# Batt_Meas.net
KiCad netlist of a schematic drawn in Altium Designer
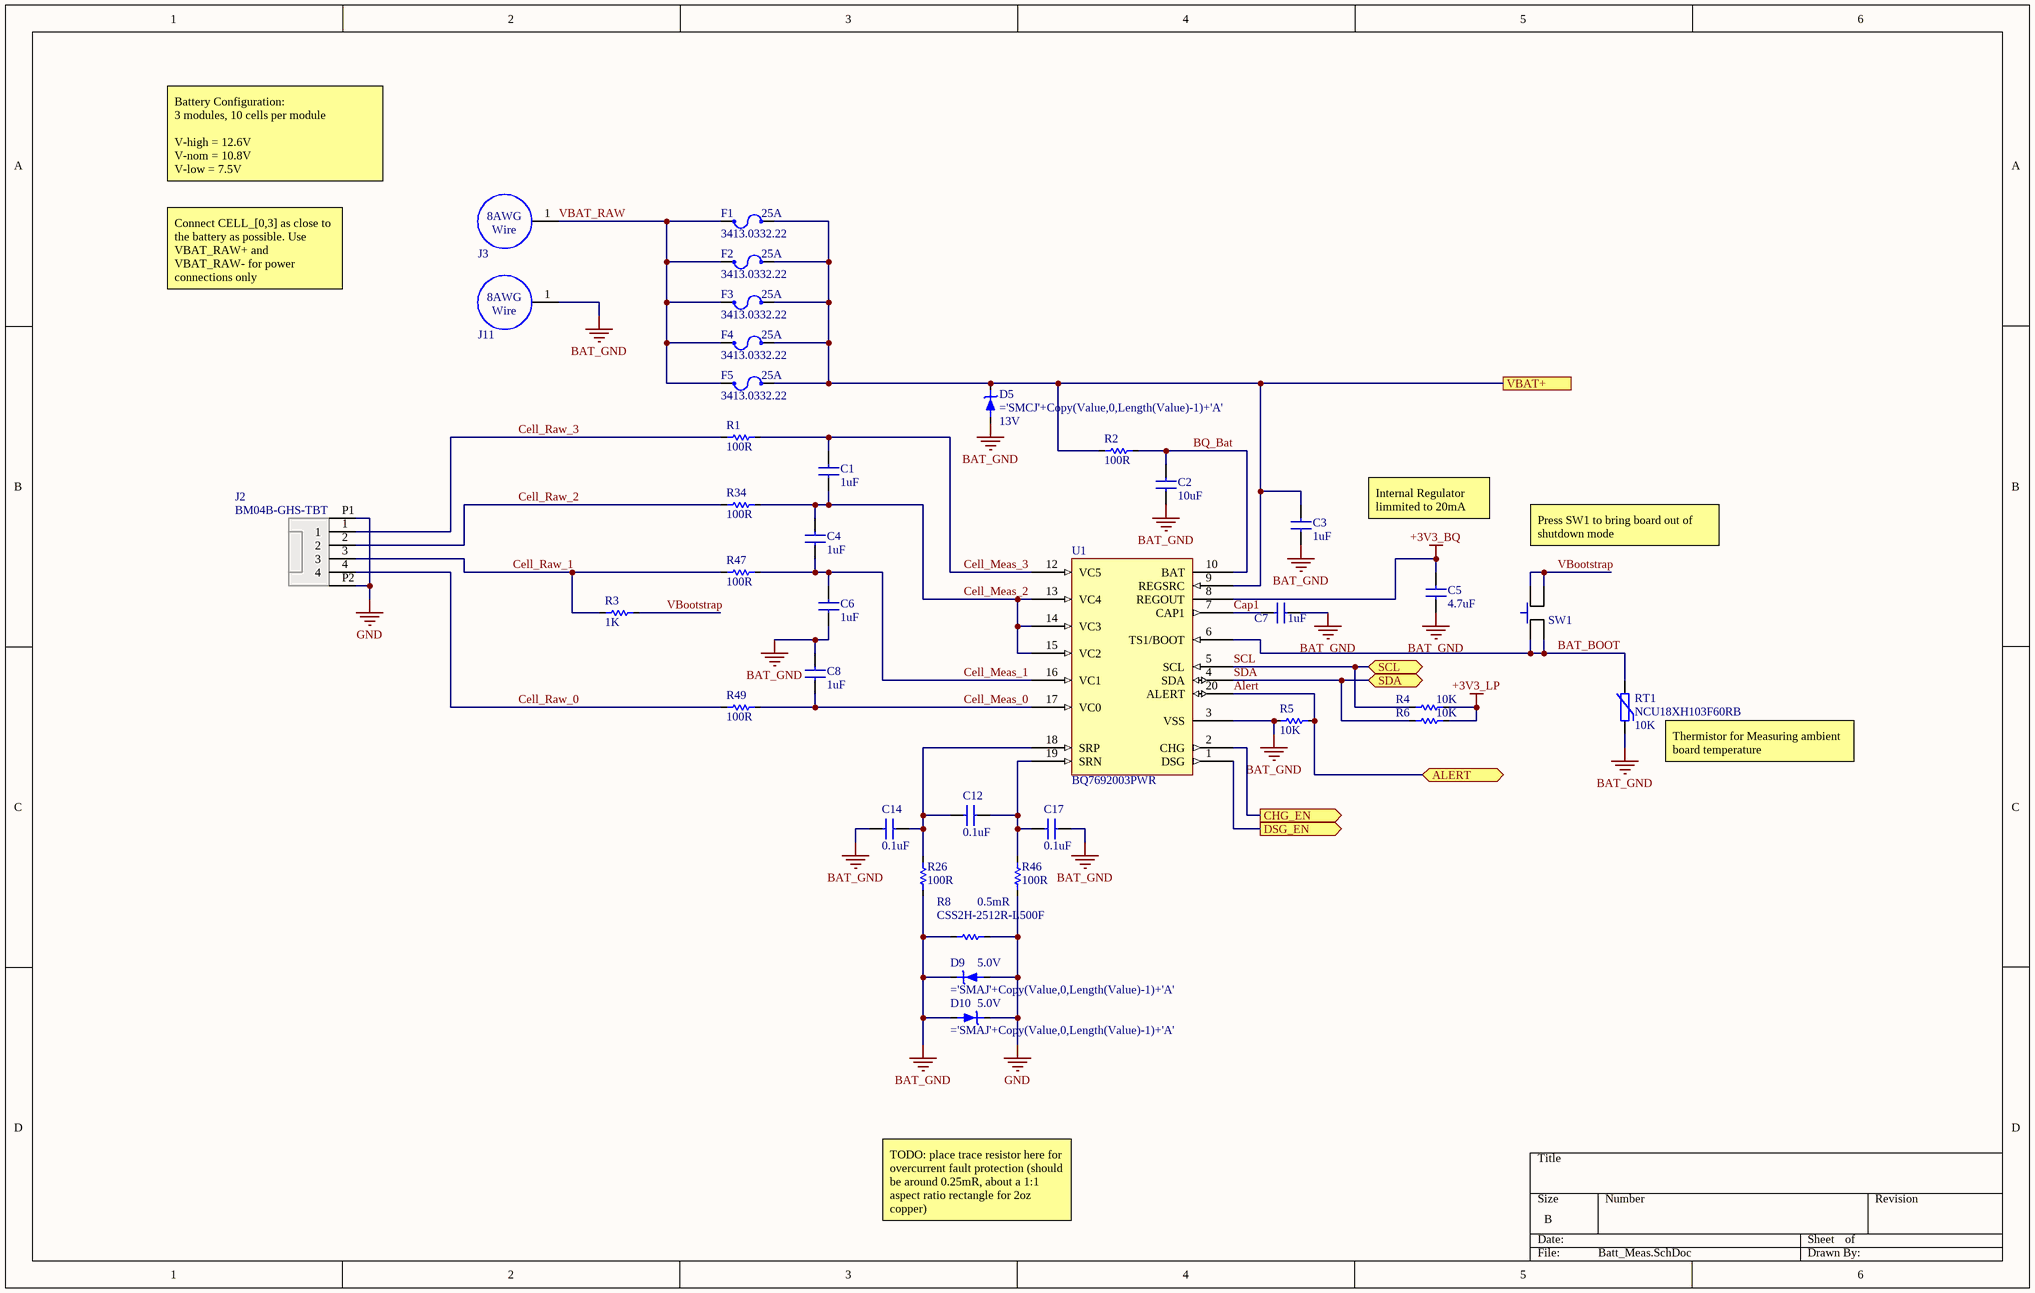
[diagram p0: Batt_Meas.SchDoc]

(export (version "E")
  (design (tool "Eeschema 10.0.6"))
  (components
    (comp (ref "C1")
      (value "1uF")
      (footprint "0603_CAPACITOR")
      (description "CAP CERM 1uF 10% 16V 0603")
      (fields
        (field (name "VOLTAGE") "16V")
        (field (name "Comment") "CAP 1uF 16V X7R")
        (field (name "SVP CREATOR") "Spencer Berglund")
      )
      (libsource (lib "capacitor") (part "C_0603_1uF_16V_10%"))
    )
    (comp (ref "C2")
      (value "10uF")
      (footprint "1206_CAPACITOR")
      (description "CAP CERM 10uF 20% 50V 1206")
      (fields
        (field (name "VOLTAGE") "50V")
        (field (name "Comment") "CAP 10uF 50V X5R")
        (field (name "SVP CREATOR") "Spencer Berglund")
      )
      (libsource (lib "capacitor") (part "C_1206_10uF_50V_20%"))
    )
    (comp (ref "C3")
      (value "1uF")
      (footprint "0603_CAPACITOR")
      (description "CAP CERM 1uF 10% 16V 0603")
      (fields
        (field (name "VOLTAGE") "16V")
        (field (name "Comment") "CAP 1uF 16V X7R")
        (field (name "SVP CREATOR") "Spencer Berglund")
      )
      (libsource (lib "capacitor") (part "C_0603_1uF_16V_10%"))
    )
    (comp (ref "C4")
      (value "1uF")
      (footprint "0603_CAPACITOR")
      (description "CAP CERM 1uF 10% 16V 0603")
      (fields
        (field (name "VOLTAGE") "16V")
        (field (name "Comment") "CAP 1uF 16V X7R")
        (field (name "SVP CREATOR") "Spencer Berglund")
      )
      (libsource (lib "capacitor") (part "C_0603_1uF_16V_10%"))
    )
    (comp (ref "C5")
      (value "4.7uF")
      (footprint "0603_Capacitor")
      (description "CAP CER 4.7UF 6.3V X5R 0603")
      (fields (field (name "VOLTAGE") "6.3V") (field (name "Comment") "CAP 4.7uF 6.3V X5R"))
      (libsource (lib "capacitor") (part "C_0603_4.7uF_6.3V_10%"))
    )
    (comp (ref "C6")
      (value "1uF")
      (footprint "0603_CAPACITOR")
      (description "CAP CERM 1uF 10% 16V 0603")
      (fields
        (field (name "VOLTAGE") "16V")
        (field (name "Comment") "CAP 1uF 16V X7R")
        (field (name "SVP CREATOR") "Spencer Berglund")
      )
      (libsource (lib "capacitor") (part "C_0603_1uF_16V_10%"))
    )
    (comp (ref "C7")
      (value "1uF")
      (footprint "0805_Capacitor")
      (description "CAP CERM 1uF 10% 16V 0805")
      (fields
        (field (name "VOLTAGE") "16V")
        (field (name "Comment") "CAP 1uF 16V X7R")
        (field (name "SVP CREATOR") "Spencer Berglund")
      )
      (libsource (lib "capacitor") (part "C_0805_1uF_16V_10%"))
    )
    (comp (ref "C8")
      (value "1uF")
      (footprint "0603_CAPACITOR")
      (description "CAP CERM 1uF 10% 16V 0603")
      (fields
        (field (name "VOLTAGE") "16V")
        (field (name "Comment") "CAP 1uF 16V X7R")
        (field (name "SVP CREATOR") "Spencer Berglund")
      )
      (libsource (lib "capacitor") (part "C_0603_1uF_16V_10%"))
    )
    (comp (ref "C12")
      (value "0.1uF")
      (footprint "0402_CAPACITOR")
      (description "CAP CERM 0.1uF 10% 16V 0402")
      (fields (field (name "VOLTAGE") "16V") (field (name "Comment") "CAP 0.1uF 16V X7R"))
      (libsource (lib "capacitor") (part "C_0402_0.1uF_16V_10%"))
    )
    (comp (ref "C14")
      (value "0.1uF")
      (footprint "0402_CAPACITOR")
      (description "CAP CERM 0.1uF 10% 16V 0402")
      (fields (field (name "VOLTAGE") "16V") (field (name "Comment") "CAP 0.1uF 16V X7R"))
      (libsource (lib "capacitor") (part "C_0402_0.1uF_16V_10%"))
    )
    (comp (ref "C17")
      (value "0.1uF")
      (footprint "0402_CAPACITOR")
      (description "CAP CERM 0.1uF 10% 16V 0402")
      (fields (field (name "VOLTAGE") "16V") (field (name "Comment") "CAP 0.1uF 16V X7R"))
      (libsource (lib "capacitor") (part "C_0402_0.1uF_16V_10%"))
    )
    (comp (ref "D5")
      (value "13V")
      (footprint "SMC")
      (description "SMC Unidirectional TVS Diode")
      (fields
        (field (name "MANUFACTURER") "Vishay")
        (field (name "MANUFACTURER PN") "SMCJA")
        (field (name "Comment") "TVS Diode")
      )
      (libsource (lib "diode") (part "D_TVS_SMCJ_Uni_generic"))
    )
    (comp (ref "D9")
      (value "5.0V")
      (footprint "SMA")
      (description "SMA Unidirectional TVS Diode")
      (fields
        (field (name "MANUFACTURER") "Vishay")
        (field (name "MANUFACTURER PN") "SMAJA")
        (field (name "Comment") "TVS Diode")
      )
      (libsource (lib "diode") (part "D_TVS_SMAJ_Uni_generic"))
    )
    (comp (ref "D10")
      (value "5.0V")
      (footprint "SMA")
      (description "SMA Unidirectional TVS Diode")
      (fields
        (field (name "MANUFACTURER") "Vishay")
        (field (name "MANUFACTURER PN") "SMAJA")
        (field (name "Comment") "TVS Diode")
      )
      (libsource (lib "diode") (part "D_TVS_SMAJ_Uni_generic"))
    )
    (comp (ref "F1")
      (value "3413.0332.22")
      (footprint "1206_Fuse")
      (description "FUSE BOARD MOUNT 25A 32VAC 63VDC")
      (fields (field (name "ALTIUM_VALUE") "25A"))
      (libsource (lib "fuse") (part "F_3413.0332.22"))
    )
    (comp (ref "F2")
      (value "3413.0332.22")
      (footprint "1206_Fuse")
      (description "FUSE BOARD MOUNT 25A 32VAC 63VDC")
      (fields (field (name "ALTIUM_VALUE") "25A"))
      (libsource (lib "fuse") (part "F_3413.0332.22"))
    )
    (comp (ref "F3")
      (value "3413.0332.22")
      (footprint "1206_Fuse")
      (description "FUSE BOARD MOUNT 25A 32VAC 63VDC")
      (fields (field (name "ALTIUM_VALUE") "25A"))
      (libsource (lib "fuse") (part "F_3413.0332.22"))
    )
    (comp (ref "F4")
      (value "3413.0332.22")
      (footprint "1206_Fuse")
      (description "FUSE BOARD MOUNT 25A 32VAC 63VDC")
      (fields (field (name "ALTIUM_VALUE") "25A"))
      (libsource (lib "fuse") (part "F_3413.0332.22"))
    )
    (comp (ref "F5")
      (value "3413.0332.22")
      (footprint "1206_Fuse")
      (description "FUSE BOARD MOUNT 25A 32VAC 63VDC")
      (fields (field (name "ALTIUM_VALUE") "25A"))
      (libsource (lib "fuse") (part "F_3413.0332.22"))
    )
    (comp (ref "J2")
      (value "BM04B-GHS-TBT")
      (footprint "J_BM04B-GHS-TBT")
      (description "Connector Header Surface Mount 4 position 0.049\" (1.25mm)")
      (fields
        (field (name "MANUFACTURER") "JST")
        (field (name "MANUFACTURER PART NUMBER") "BM04B-GHS-TBT(LF)(SN)")
      )
      (libsource (lib "connector") (part "J_BM04B-GHS-TBT"))
    )
    (comp (ref "J3")
      (value "8AWG Wire To Board")
      (footprint "Wire_To_Board_8AWG_Red")
      (description "8AWG Stranded Wire Thru-Hole Pad")
      (libsource (lib "connector") (part "J_Wire_To_Board_8AWG"))
    )
    (comp (ref "J11")
      (value "8AWG Wire To Board")
      (footprint "Wire_To_Board_8AWG_Black")
      (description "8AWG Stranded Wire Thru-Hole Pad")
      (libsource (lib "connector") (part "J_Wire_To_Board_8AWG"))
    )
    (comp (ref "R1")
      (value "100R")
      (footprint "0402_Resistor")
      (description "Generic 0402 Resistor (10.2R to 10M)")
      (fields (field (name "TOLERANCE") "±1%") (field (name "MANUFACTURER") "Yageo"))
      (libsource (lib "resistor") (part "R_0402_generic_1%"))
    )
    (comp (ref "R2")
      (value "100R")
      (footprint "0402_Resistor")
      (description "Generic 0402 Resistor (10.2R to 10M)")
      (fields (field (name "TOLERANCE") "±1%") (field (name "MANUFACTURER") "Yageo"))
      (libsource (lib "resistor") (part "R_0402_generic_1%"))
    )
    (comp (ref "R3")
      (value "1K")
      (footprint "0402_Resistor")
      (description "Generic 0402 Resistor (10.2R to 10M)")
      (fields (field (name "TOLERANCE") "±1%") (field (name "MANUFACTURER") "Yageo"))
      (libsource (lib "resistor") (part "R_0402_generic_1%"))
    )
    (comp (ref "R4")
      (value "10K")
      (footprint "0402_Resistor")
      (description "Generic 0402 Resistor (10.2R to 10M)")
      (fields (field (name "TOLERANCE") "±1%") (field (name "MANUFACTURER") "Yageo"))
      (libsource (lib "resistor") (part "R_0402_generic_1%"))
    )
    (comp (ref "R5")
      (value "10K")
      (footprint "0402_Resistor")
      (description "Generic 0402 Resistor (10.2R to 10M)")
      (fields (field (name "TOLERANCE") "±1%") (field (name "MANUFACTURER") "Yageo"))
      (libsource (lib "resistor") (part "R_0402_generic_1%"))
    )
    (comp (ref "R6")
      (value "10K")
      (footprint "0402_Resistor")
      (description "Generic 0402 Resistor (10.2R to 10M)")
      (fields (field (name "TOLERANCE") "±1%") (field (name "MANUFACTURER") "Yageo"))
      (libsource (lib "resistor") (part "R_0402_generic_1%"))
    )
    (comp (ref "R8")
      (value "CSS2H-2512R-L500F")
      (footprint "2512_Resistor")
      (description "500 µOhms ±1% 6W Chip Resistor 2512 (6432 Metric) Current Sense, Moisture Resistant Metal Element")
      (fields
        (field (name "TOLERANCE") "1%")
        (field (name "MANUFACTURER") "Bourns")
        (field (name "ALTIUM_VALUE") "0.5mR")
      )
      (libsource (lib "resistor") (part "R_CSS2H-2512R-L500F"))
    )
    (comp (ref "R26")
      (value "100R")
      (footprint "0402_Resistor")
      (description "Generic 0402 Resistor (10.2R to 10M)")
      (fields (field (name "TOLERANCE") "±1%") (field (name "MANUFACTURER") "Yageo"))
      (libsource (lib "resistor") (part "R_0402_generic_1%"))
    )
    (comp (ref "R34")
      (value "100R")
      (footprint "0402_Resistor")
      (description "Generic 0402 Resistor (10.2R to 10M)")
      (fields (field (name "TOLERANCE") "±1%") (field (name "MANUFACTURER") "Yageo"))
      (libsource (lib "resistor") (part "R_0402_generic_1%"))
    )
    (comp (ref "R46")
      (value "100R")
      (footprint "0402_Resistor")
      (description "Generic 0402 Resistor (10.2R to 10M)")
      (fields (field (name "TOLERANCE") "±1%") (field (name "MANUFACTURER") "Yageo"))
      (libsource (lib "resistor") (part "R_0402_generic_1%"))
    )
    (comp (ref "R47")
      (value "100R")
      (footprint "0402_Resistor")
      (description "Generic 0402 Resistor (10.2R to 10M)")
      (fields (field (name "TOLERANCE") "±1%") (field (name "MANUFACTURER") "Yageo"))
      (libsource (lib "resistor") (part "R_0402_generic_1%"))
    )
    (comp (ref "R49")
      (value "100R")
      (footprint "0402_Resistor")
      (description "Generic 0402 Resistor (10.2R to 10M)")
      (fields (field (name "TOLERANCE") "±1%") (field (name "MANUFACTURER") "Yageo"))
      (libsource (lib "resistor") (part "R_0402_generic_1%"))
    )
    (comp (ref "RT1")
      (value "NCU18XH103F60RB")
      (footprint "0603_Resistor")
      (description "NTC Thermistor 10k 0603 (1608 Metric)")
      (fields (field (name "MANUFACTURER") "Murata") (field (name "ALTIUM_VALUE") "10K"))
      (libsource (lib "resistor") (part "RT_NCU18XH103F60RB"))
    )
    (comp (ref "SW1")
      (value "SW_TACT_SWITCH_6x6")
      (footprint "SW_6x6mm_SMD")
      (description "SWITCH TACT 6MM BLACK 160GF")
      (fields (field (name "SVP CREATOR") "Spencer Berglund"))
      (libsource (lib "misc") (part "SW_TACT_SWITCH_6x6"))
    )
    (comp (ref "U1")
      (value "BQ7692003PWR")
      (footprint "TSSOP-20")
      (description "Battery Battery Monitor IC Multi-Chemistry 20-TSSOP")
      (libsource (lib "ic") (part "U_BQ7692003PWR"))
    )
  )
  (nets
    (net (code "1") (name "+3V3_BQ") (class "Default")
      (node (ref "C5") (pin "1") (pinfunction "1_1") (pintype "passive"))
      (node (ref "U1") (pin "8") (pinfunction "REGOUT_8") (pintype "power_in"))
    )
    (net (code "2") (name "+3V3_LP") (class "Default")
      (node (ref "R4") (pin "1") (pinfunction "1_1") (pintype "passive"))
      (node (ref "R6") (pin "1") (pinfunction "1_1") (pintype "passive"))
    )
    (net (code "3") (name "/Alert") (class "Default")
      (node (ref "R5") (pin "2") (pinfunction "2_2") (pintype "passive"))
      (node (ref "U1") (pin "20") (pinfunction "ALERT_20") (pintype "bidirectional"))
    )
    (net (code "4") (name "/BAT_BOOT") (class "Default")
      (node (ref "RT1") (pin "2") (pinfunction "2_2") (pintype "passive"))
      (node (ref "SW1") (pin "1") (pinfunction "1_1") (pintype "passive"))
      (node (ref "SW1") (pin "4") (pinfunction "4_4") (pintype "passive"))
      (node (ref "U1") (pin "6") (pinfunction "TS1/BOOT_6") (pintype "input"))
    )
    (net (code "5") (name "/BQ_Bat") (class "Default")
      (node (ref "C2") (pin "1") (pinfunction "1_1") (pintype "passive"))
      (node (ref "R2") (pin "1") (pinfunction "1_1") (pintype "passive"))
      (node (ref "U1") (pin "10") (pinfunction "BAT_10") (pintype "power_in"))
    )
    (net (code "6") (name "/CHG_EN") (class "Default")
      (node (ref "U1") (pin "2") (pinfunction "CHG_2") (pintype "output"))
    )
    (net (code "7") (name "/Cap1") (class "Default")
      (node (ref "C7") (pin "2") (pinfunction "2_2") (pintype "passive"))
      (node (ref "U1") (pin "7") (pinfunction "CAP1_7") (pintype "output"))
    )
    (net (code "8") (name "/Cell_Meas_0") (class "Default")
      (node (ref "C8") (pin "2") (pinfunction "2_2") (pintype "passive"))
      (node (ref "R49") (pin "2") (pinfunction "2_2") (pintype "passive"))
      (node (ref "U1") (pin "17") (pinfunction "VC0_17") (pintype "input"))
    )
    (net (code "9") (name "/Cell_Meas_1") (class "Default")
      (node (ref "C4") (pin "2") (pinfunction "2_2") (pintype "passive"))
      (node (ref "C6") (pin "1") (pinfunction "1_1") (pintype "passive"))
      (node (ref "R47") (pin "2") (pinfunction "2_2") (pintype "passive"))
      (node (ref "U1") (pin "16") (pinfunction "VC1_16") (pintype "input"))
    )
    (net (code "10") (name "/Cell_Meas_2") (class "Default")
      (node (ref "C1") (pin "2") (pinfunction "2_2") (pintype "passive"))
      (node (ref "C4") (pin "1") (pinfunction "1_1") (pintype "passive"))
      (node (ref "R34") (pin "2") (pinfunction "2_2") (pintype "passive"))
      (node (ref "U1") (pin "13") (pinfunction "VC4_13") (pintype "input"))
      (node (ref "U1") (pin "14") (pinfunction "VC3_14") (pintype "input"))
      (node (ref "U1") (pin "15") (pinfunction "VC2_15") (pintype "input"))
    )
    (net (code "11") (name "/Cell_Meas_3") (class "Default")
      (node (ref "C1") (pin "1") (pinfunction "1_1") (pintype "passive"))
      (node (ref "R1") (pin "2") (pinfunction "2_2") (pintype "passive"))
      (node (ref "U1") (pin "12") (pinfunction "VC5_12") (pintype "input"))
    )
    (net (code "12") (name "/Cell_Raw_0") (class "Default")
      (node (ref "J2") (pin "4") (pinfunction "4_4") (pintype "passive"))
      (node (ref "R49") (pin "1") (pinfunction "1_1") (pintype "passive"))
    )
    (net (code "13") (name "/Cell_Raw_1") (class "Default")
      (node (ref "J2") (pin "3") (pinfunction "3_3") (pintype "passive"))
      (node (ref "R3") (pin "1") (pinfunction "1_1") (pintype "passive"))
      (node (ref "R47") (pin "1") (pinfunction "1_1") (pintype "passive"))
    )
    (net (code "14") (name "/Cell_Raw_2") (class "Default")
      (node (ref "J2") (pin "2") (pinfunction "2_2") (pintype "passive"))
      (node (ref "R34") (pin "1") (pinfunction "1_1") (pintype "passive"))
    )
    (net (code "15") (name "/Cell_Raw_3") (class "Default")
      (node (ref "J2") (pin "1") (pinfunction "1_1") (pintype "passive"))
      (node (ref "R1") (pin "1") (pinfunction "1_1") (pintype "passive"))
    )
    (net (code "16") (name "/DSG_EN") (class "Default")
      (node (ref "U1") (pin "1") (pinfunction "DSG_1") (pintype "output"))
    )
    (net (code "17") (name "/SCL") (class "Default")
      (node (ref "R4") (pin "2") (pinfunction "2_2") (pintype "passive"))
      (node (ref "U1") (pin "5") (pinfunction "SCL_5") (pintype "input"))
    )
    (net (code "18") (name "/SDA") (class "Default")
      (node (ref "R6") (pin "2") (pinfunction "2_2") (pintype "passive"))
      (node (ref "U1") (pin "4") (pinfunction "SDA_4") (pintype "bidirectional"))
    )
    (net (code "19") (name "/VBAT+") (class "Default")
      (node (ref "C3") (pin "1") (pinfunction "1_1") (pintype "passive"))
      (node (ref "D5") (pin "2") (pinfunction "Cathode_2") (pintype "passive"))
      (node (ref "F1") (pin "2") (pinfunction "2_2") (pintype "passive"))
      (node (ref "F2") (pin "2") (pinfunction "2_2") (pintype "passive"))
      (node (ref "F3") (pin "2") (pinfunction "2_2") (pintype "passive"))
      (node (ref "F4") (pin "2") (pinfunction "2_2") (pintype "passive"))
      (node (ref "F5") (pin "2") (pinfunction "2_2") (pintype "passive"))
      (node (ref "R2") (pin "2") (pinfunction "2_2") (pintype "passive"))
      (node (ref "U1") (pin "9") (pinfunction "REGSRC_9") (pintype "input"))
    )
    (net (code "20") (name "/VBAT_RAW") (class "Default")
      (node (ref "F1") (pin "1") (pinfunction "1_1") (pintype "passive"))
      (node (ref "F2") (pin "1") (pinfunction "1_1") (pintype "passive"))
      (node (ref "F3") (pin "1") (pinfunction "1_1") (pintype "passive"))
      (node (ref "F4") (pin "1") (pinfunction "1_1") (pintype "passive"))
      (node (ref "F5") (pin "1") (pinfunction "1_1") (pintype "passive"))
      (node (ref "J3") (pin "1") (pinfunction "1_1") (pintype "passive"))
    )
    (net (code "21") (name "/VBootstrap") (class "Default")
      (node (ref "R3") (pin "2") (pinfunction "2_2") (pintype "passive"))
      (node (ref "SW1") (pin "2") (pinfunction "2_2") (pintype "passive"))
      (node (ref "SW1") (pin "3") (pinfunction "3_3") (pintype "passive"))
    )
    (net (code "22") (name "BAT_GND") (class "Default")
      (node (ref "C14") (pin "1") (pinfunction "1_1") (pintype "passive"))
      (node (ref "C17") (pin "2") (pinfunction "2_2") (pintype "passive"))
      (node (ref "C2") (pin "2") (pinfunction "2_2") (pintype "passive"))
      (node (ref "C3") (pin "2") (pinfunction "2_2") (pintype "passive"))
      (node (ref "C5") (pin "2") (pinfunction "2_2") (pintype "passive"))
      (node (ref "C6") (pin "2") (pinfunction "2_2") (pintype "passive"))
      (node (ref "C7") (pin "1") (pinfunction "1_1") (pintype "passive"))
      (node (ref "C8") (pin "1") (pinfunction "1_1") (pintype "passive"))
      (node (ref "D10") (pin "1") (pinfunction "Anode_1") (pintype "passive"))
      (node (ref "D5") (pin "1") (pinfunction "Anode_1") (pintype "passive"))
      (node (ref "D9") (pin "2") (pinfunction "Cathode_2") (pintype "passive"))
      (node (ref "J11") (pin "1") (pinfunction "1_1") (pintype "passive"))
      (node (ref "R26") (pin "2") (pinfunction "2_2") (pintype "passive"))
      (node (ref "R5") (pin "1") (pinfunction "1_1") (pintype "passive"))
      (node (ref "R8") (pin "1") (pinfunction "1_1") (pintype "passive"))
      (node (ref "RT1") (pin "1") (pinfunction "1_1") (pintype "passive"))
      (node (ref "U1") (pin "3") (pinfunction "VSS_3") (pintype "power_in"))
    )
    (net (code "23") (name "GND") (class "Default")
      (node (ref "D10") (pin "2") (pinfunction "Cathode_2") (pintype "passive"))
      (node (ref "D9") (pin "1") (pinfunction "Anode_1") (pintype "passive"))
      (node (ref "J2") (pin "P1") (pinfunction "P1_P1") (pintype "passive"))
      (node (ref "J2") (pin "P2") (pinfunction "P2_P2") (pintype "passive"))
      (node (ref "R46") (pin "2") (pinfunction "2_2") (pintype "passive"))
      (node (ref "R8") (pin "2") (pinfunction "2_2") (pintype "passive"))
    )
    (net (code "24") (name "Net-(U1-SRN)") (class "Default")
      (node (ref "C12") (pin "2") (pinfunction "2_2") (pintype "passive"))
      (node (ref "C17") (pin "1") (pinfunction "1_1") (pintype "passive"))
      (node (ref "R46") (pin "1") (pinfunction "1_1") (pintype "passive"))
      (node (ref "U1") (pin "19") (pinfunction "SRN_19") (pintype "input"))
    )
    (net (code "25") (name "Net-(U1-SRP)") (class "Default")
      (node (ref "C12") (pin "1") (pinfunction "1_1") (pintype "passive"))
      (node (ref "C14") (pin "2") (pinfunction "2_2") (pintype "passive"))
      (node (ref "R26") (pin "1") (pinfunction "1_1") (pintype "passive"))
      (node (ref "U1") (pin "18") (pinfunction "SRP_18") (pintype "input"))
    )
  )
)
